# Sheet1.net
KiCad netlist of a schematic drawn in Altium Designer
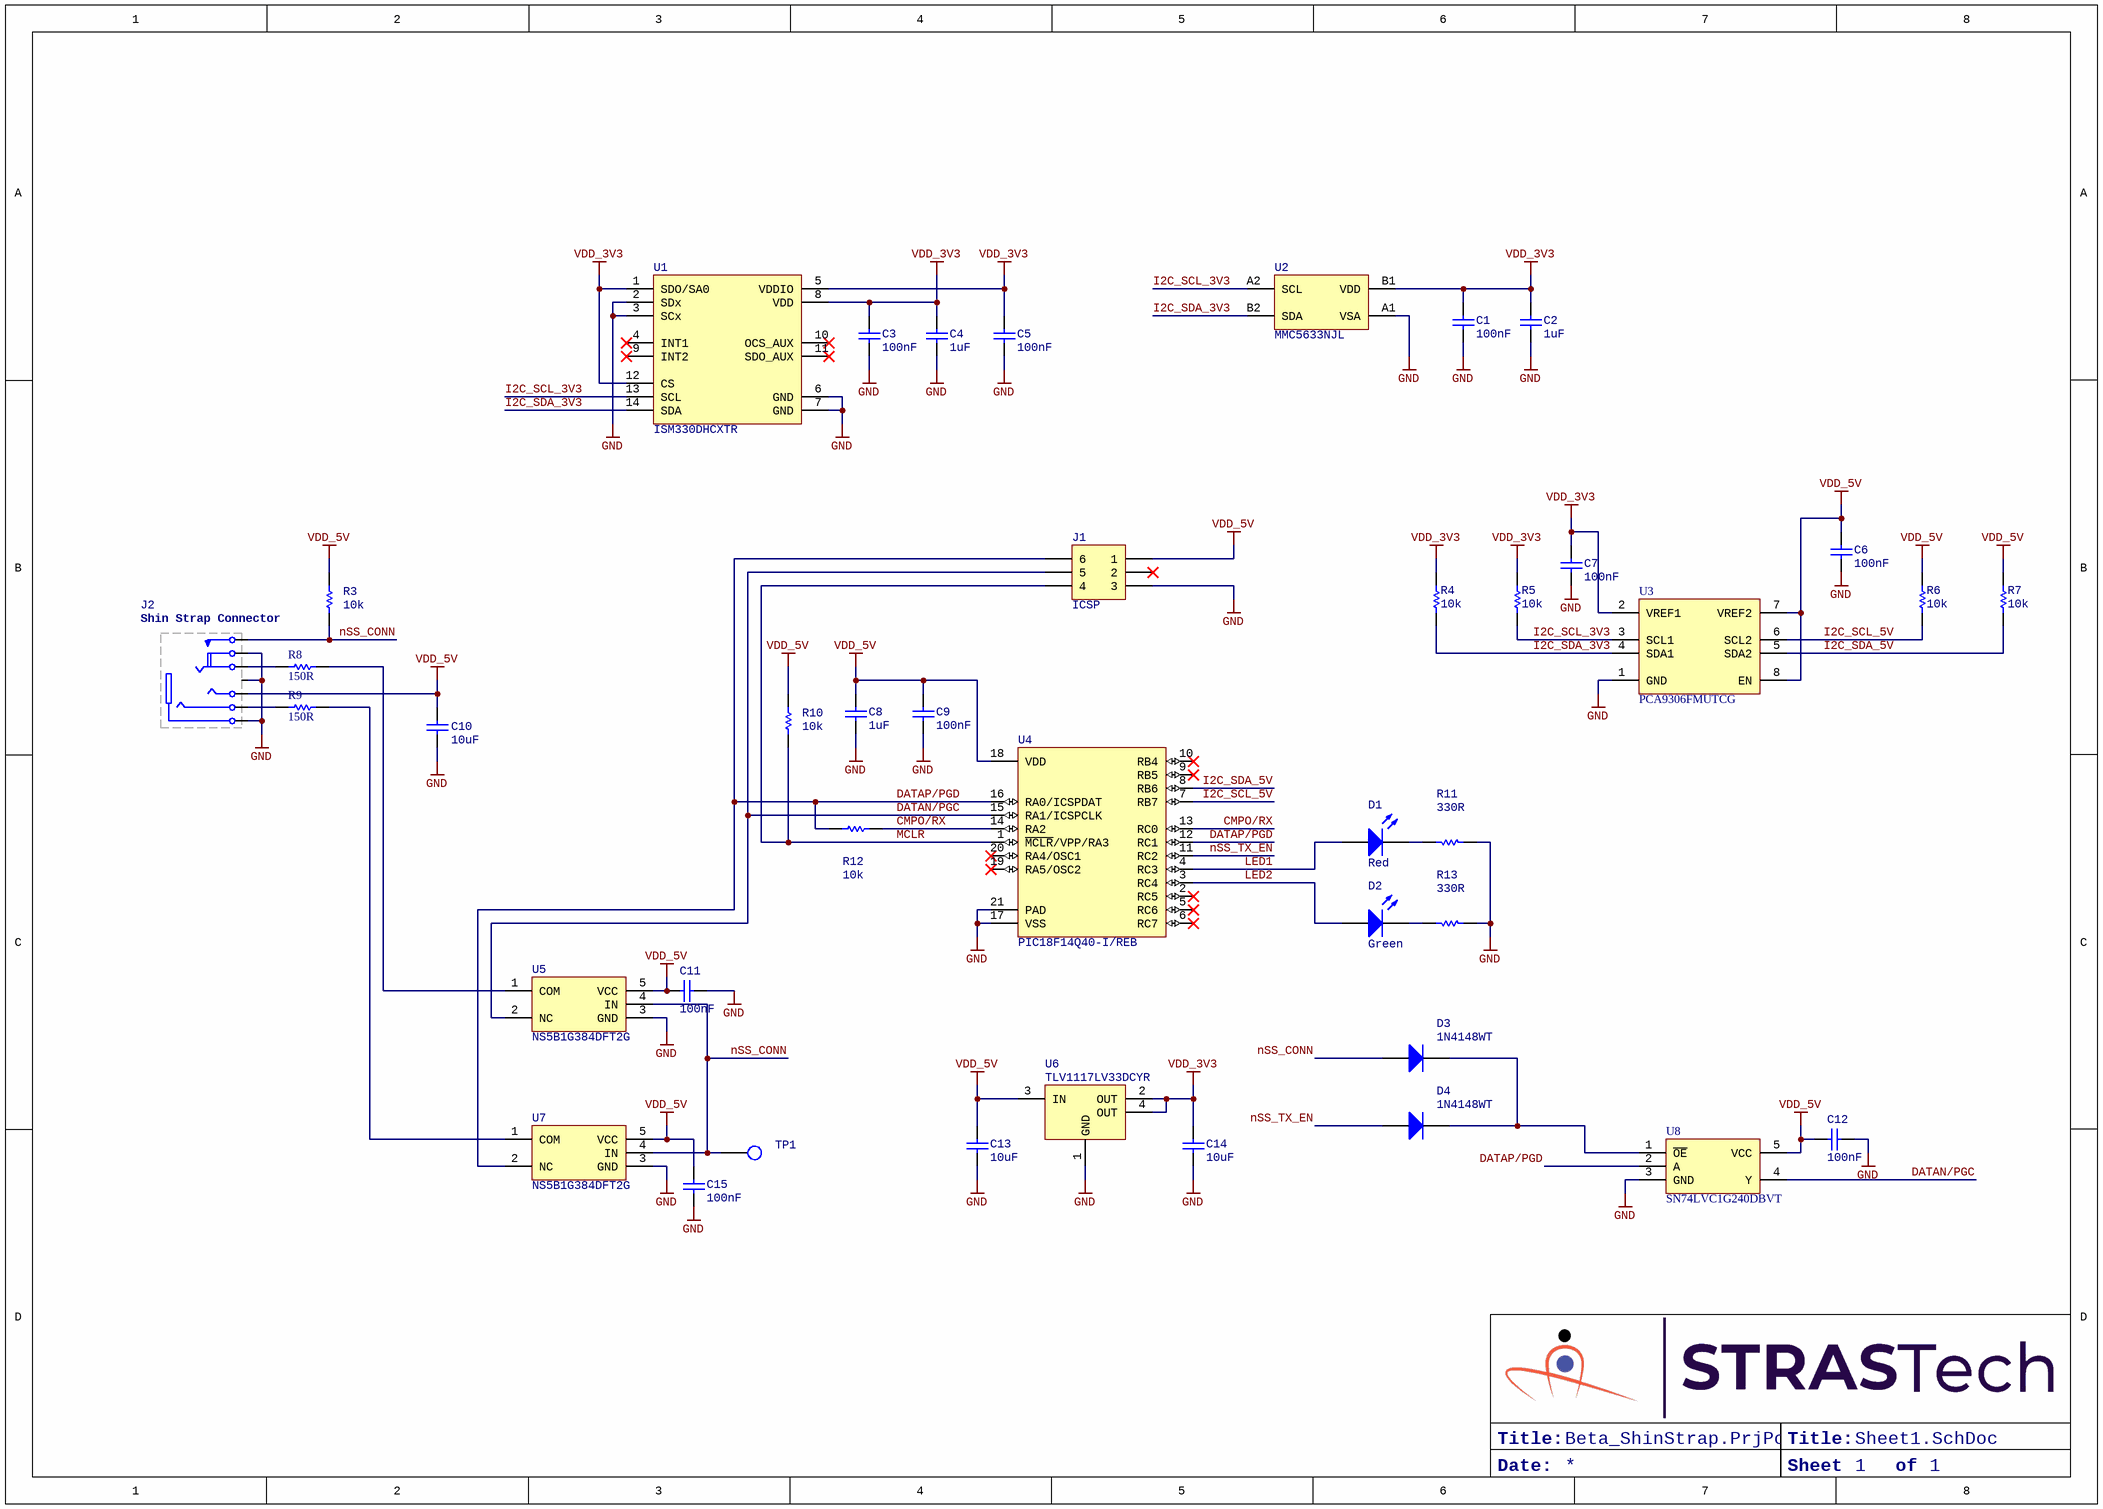
[diagram p0: Sheet1.SchDoc]

(export (version "E")
  (design (tool "Eeschema 10.0.6"))
  (components
    (comp (ref "C1")
      (value "100nF")
      (footprint "Cap,SMD,0402")
      (description "0.1µF ±10% 25V Ceramic Capacitor X7R 0402 (1005 Metric)")
      (fields
        (field (name "VENDOR PART NUMBER") "490-14603-1-ND")
        (field (name "MANUFACTURER") "Murata Electronics")
        (field (name "CREATEDBY") "Judd Foster")
      )
      (libsource (lib "symbols") (part "CAP,Cer,100nF,25VDC,X7R,0402"))
    )
    (comp (ref "C2")
      (value "1uF")
      (footprint "Cap,SMD,0402")
      (description "1 µF ±10% 35V Ceramic Capacitor X5R 0402 (1005 Metric)")
      (fields
        (field (name "VENDOR PART NUMBER") "445-9073-1-ND")
        (field (name "MANUFACTURER") "TDK Corporation")
        (field (name "CREATEDBY") "Judd Foster")
      )
      (libsource (lib "symbols") (part "CAP,Cer,1uF,35VDC,X5R,0402"))
    )
    (comp (ref "C3")
      (value "100nF")
      (footprint "Cap,SMD,0402")
      (description "0.1µF ±10% 25V Ceramic Capacitor X7R 0402 (1005 Metric)")
      (fields
        (field (name "VENDOR PART NUMBER") "490-14603-1-ND")
        (field (name "MANUFACTURER") "Murata Electronics")
        (field (name "CREATEDBY") "Judd Foster")
      )
      (libsource (lib "symbols") (part "CAP,Cer,100nF,25VDC,X7R,0402"))
    )
    (comp (ref "C4")
      (value "1uF")
      (footprint "Cap,SMD,0402")
      (description "1 µF ±10% 35V Ceramic Capacitor X5R 0402 (1005 Metric)")
      (fields
        (field (name "VENDOR PART NUMBER") "445-9073-1-ND")
        (field (name "MANUFACTURER") "TDK Corporation")
        (field (name "CREATEDBY") "Judd Foster")
      )
      (libsource (lib "symbols") (part "CAP,Cer,1uF,35VDC,X5R,0402"))
    )
    (comp (ref "C5")
      (value "100nF")
      (footprint "Cap,SMD,0402")
      (description "0.1µF ±10% 25V Ceramic Capacitor X7R 0402 (1005 Metric)")
      (fields
        (field (name "VENDOR PART NUMBER") "490-14603-1-ND")
        (field (name "MANUFACTURER") "Murata Electronics")
        (field (name "CREATEDBY") "Judd Foster")
      )
      (libsource (lib "symbols") (part "CAP,Cer,100nF,25VDC,X7R,0402"))
    )
    (comp (ref "C6")
      (value "100nF")
      (footprint "Cap,SMD,0402")
      (description "0.1µF ±10% 25V Ceramic Capacitor X7R 0402 (1005 Metric)")
      (fields
        (field (name "VENDOR PART NUMBER") "490-14603-1-ND")
        (field (name "MANUFACTURER") "Murata Electronics")
        (field (name "CREATEDBY") "Judd Foster")
      )
      (libsource (lib "symbols") (part "CAP,Cer,100nF,25VDC,X7R,0402"))
    )
    (comp (ref "C7")
      (value "100nF")
      (footprint "Cap,SMD,0402")
      (description "0.1µF ±10% 25V Ceramic Capacitor X7R 0402 (1005 Metric)")
      (fields
        (field (name "VENDOR PART NUMBER") "490-14603-1-ND")
        (field (name "MANUFACTURER") "Murata Electronics")
        (field (name "CREATEDBY") "Judd Foster")
      )
      (libsource (lib "symbols") (part "CAP,Cer,100nF,25VDC,X7R,0402"))
    )
    (comp (ref "C8")
      (value "1uF")
      (footprint "Cap,SMD,0402")
      (description "1 µF ±10% 35V Ceramic Capacitor X5R 0402 (1005 Metric)")
      (fields
        (field (name "VENDOR PART NUMBER") "445-9073-1-ND")
        (field (name "MANUFACTURER") "TDK Corporation")
        (field (name "CREATEDBY") "Judd Foster")
      )
      (libsource (lib "symbols") (part "CAP,Cer,1uF,35VDC,X5R,0402"))
    )
    (comp (ref "C9")
      (value "100nF")
      (footprint "Cap,SMD,0402")
      (description "0.1µF ±10% 25V Ceramic Capacitor X7R 0402 (1005 Metric)")
      (fields
        (field (name "VENDOR PART NUMBER") "490-14603-1-ND")
        (field (name "MANUFACTURER") "Murata Electronics")
        (field (name "CREATEDBY") "Judd Foster")
      )
      (libsource (lib "symbols") (part "CAP,Cer,100nF,25VDC,X7R,0402"))
    )
    (comp (ref "C10")
      (value "10uF")
      (footprint "Cap,SMD,0402")
      (description "10 µF ±20% 10V Ceramic Capacitor X5R 0402 (1005 Metric)")
      (fields
        (field (name "VENDOR PART NUMBER") "1276-1450-1-ND")
        (field (name "MANUFACTURER") "Samsung Electro-Mechanics")
        (field (name "CREATEDBY") "Judd Foster")
      )
      (libsource (lib "symbols") (part "CAP,Cer,10uF,10VDC,X5R,0402"))
    )
    (comp (ref "C11")
      (value "100nF")
      (footprint "Cap,SMD,0402")
      (description "0.1µF ±10% 25V Ceramic Capacitor X7R 0402 (1005 Metric)")
      (fields
        (field (name "VENDOR PART NUMBER") "490-14603-1-ND")
        (field (name "MANUFACTURER") "Murata Electronics")
        (field (name "CREATEDBY") "Judd Foster")
      )
      (libsource (lib "symbols") (part "CAP,Cer,100nF,25VDC,X7R,0402"))
    )
    (comp (ref "C12")
      (value "100nF")
      (footprint "Cap,SMD,0402")
      (description "0.1µF ±10% 25V Ceramic Capacitor X7R 0402 (1005 Metric)")
      (fields
        (field (name "VENDOR PART NUMBER") "490-14603-1-ND")
        (field (name "MANUFACTURER") "Murata Electronics")
        (field (name "CREATEDBY") "Judd Foster")
      )
      (libsource (lib "symbols") (part "CAP,Cer,100nF,25VDC,X7R,0402"))
    )
    (comp (ref "C13")
      (value "10uF")
      (footprint "Cap,SMD,0402")
      (description "10 µF ±20% 10V Ceramic Capacitor X5R 0402 (1005 Metric)")
      (fields
        (field (name "VENDOR PART NUMBER") "1276-1450-1-ND")
        (field (name "MANUFACTURER") "Samsung Electro-Mechanics")
        (field (name "CREATEDBY") "Judd Foster")
      )
      (libsource (lib "symbols") (part "CAP,Cer,10uF,10VDC,X5R,0402"))
    )
    (comp (ref "C14")
      (value "10uF")
      (footprint "Cap,SMD,0402")
      (description "10 µF ±20% 10V Ceramic Capacitor X5R 0402 (1005 Metric)")
      (fields
        (field (name "VENDOR PART NUMBER") "1276-1450-1-ND")
        (field (name "MANUFACTURER") "Samsung Electro-Mechanics")
        (field (name "CREATEDBY") "Judd Foster")
      )
      (libsource (lib "symbols") (part "CAP,Cer,10uF,10VDC,X5R,0402"))
    )
    (comp (ref "C15")
      (value "100nF")
      (footprint "Cap,SMD,0402")
      (description "0.1µF ±10% 25V Ceramic Capacitor X7R 0402 (1005 Metric)")
      (fields
        (field (name "VENDOR PART NUMBER") "490-14603-1-ND")
        (field (name "MANUFACTURER") "Murata Electronics")
        (field (name "CREATEDBY") "Judd Foster")
      )
      (libsource (lib "symbols") (part "CAP,Cer,100nF,25VDC,X7R,0402"))
    )
    (comp (ref "D1")
      (value "Red")
      (footprint "LED,0603")
      (description "Red 633nm LED Indication - Discrete 2V 0603 (1608 Metric)")
      (fields
        (field (name "MANUFACTURER") "Lite-On Inc.")
        (field (name "MANUFACTURER PART NUMBER") "LS Q976-NR-1")
        (field (name "CREATEDBY") "Judd Foster")
      )
      (libsource (lib "symbols") (part "LED,Red,SMD,0603"))
    )
    (comp (ref "D2")
      (value "Green")
      (footprint "LED,0603")
      (description "Green 530nm LED Indication - Discrete 3V 0603 (1608 Metric)")
      (fields
        (field (name "MANUFACTURER") "Stanley Electric Co")
        (field (name "MANUFACTURER PART NUMBER") "THG1111C-0005-TR")
        (field (name "CREATEDBY") "Judd Foster")
      )
      (libsource (lib "symbols") (part "LED,Green,SMD,0603"))
    )
    (comp (ref "D3")
      (value "1N4148WT")
      (footprint "SOD523")
      (description "Diode Standard 75 V 200mA Surface Mount SOD-523F")
      (fields
        (field (name "MANUFACTURER") "ON Semiconductor")
        (field (name "VENDOR PART NUMBER") "1N4148WTCT-ND")
        (field (name "CREATEDBY") "Judd Foster")
      )
      (libsource (lib "symbols") (part "DIODE,Gen,75V,200mA,SOD523F"))
    )
    (comp (ref "D4")
      (value "1N4148WT")
      (footprint "SOD523")
      (description "Diode Standard 75 V 200mA Surface Mount SOD-523F")
      (fields
        (field (name "MANUFACTURER") "ON Semiconductor")
        (field (name "VENDOR PART NUMBER") "1N4148WTCT-ND")
        (field (name "CREATEDBY") "Judd Foster")
      )
      (libsource (lib "symbols") (part "DIODE,Gen,75V,200mA,SOD523F"))
    )
    (comp (ref "J1")
      (value "Term,Header,3x2 Pin,1.27mm,SMD")
      (footprint "TERM,HEADER,3X2PIN,P1.27,SMD")
      (description "Connector Header Surface Mount 6 position 0.050\" (1.27mm)")
      (fields
        (field (name "VENDOR PART NUMBER") "609-3693-1-ND")
        (field (name "MANUFACTURER") "Amphenol ICC (FCI)")
        (field (name "CREATEDBY") "Judd Foster")
      )
      (libsource (lib "symbols") (part "Term,Header,3x2 Pin,1.27mm,SMD"))
    )
    (comp (ref "J2")
      (value "Conn,Jack,TRS,3.5mm,Thru,Shielded")
      (footprint "Conn,Jack,TRS,3.5mm,Thru,Shielded")
      (fields
        (field (name "MANUFACTURER") "CUI Devices")
        (field (name "MANUFACTURER PART NUMBER") "SJ-435107RS")
        (field (name "VENDOR PART NUMBER") "CP-435107RS-ND")
        (field (name "CREATEDBY") "Judd Foster")
      )
      (libsource (lib "symbols") (part "Conn,Jack,TRS,3.5mm,Thru,Shielded"))
    )
    (comp (ref "R3")
      (value "10k")
      (footprint "RES,0402")
      (description "10 kOhms ±5% 0.063W, 1/16W Chip Resistor 0402 (1005 Metric) Automotive AEC-Q200 Thick Film")
      (fields
        (field (name "VENDOR PART NUMBER") "RMCF0402JT10K0CT-ND")
        (field (name "MANUFACTURER") "Stackpole Electronics Inc")
        (field (name "CREATEDBY") "Judd Foster")
      )
      (libsource (lib "symbols") (part "RES,10k,5%,0.063W,0402"))
    )
    (comp (ref "R4")
      (value "10k")
      (footprint "RES,0402")
      (description "10 kOhms ±5% 0.063W, 1/16W Chip Resistor 0402 (1005 Metric) Automotive AEC-Q200 Thick Film")
      (fields
        (field (name "VENDOR PART NUMBER") "RMCF0402JT10K0CT-ND")
        (field (name "MANUFACTURER") "Stackpole Electronics Inc")
        (field (name "CREATEDBY") "Judd Foster")
      )
      (libsource (lib "symbols") (part "RES,10k,5%,0.063W,0402"))
    )
    (comp (ref "R5")
      (value "10k")
      (footprint "RES,0402")
      (description "10 kOhms ±5% 0.063W, 1/16W Chip Resistor 0402 (1005 Metric) Automotive AEC-Q200 Thick Film")
      (fields
        (field (name "VENDOR PART NUMBER") "RMCF0402JT10K0CT-ND")
        (field (name "MANUFACTURER") "Stackpole Electronics Inc")
        (field (name "CREATEDBY") "Judd Foster")
      )
      (libsource (lib "symbols") (part "RES,10k,5%,0.063W,0402"))
    )
    (comp (ref "R6")
      (value "10k")
      (footprint "RES,0402")
      (description "10 kOhms ±5% 0.063W, 1/16W Chip Resistor 0402 (1005 Metric) Automotive AEC-Q200 Thick Film")
      (fields
        (field (name "VENDOR PART NUMBER") "RMCF0402JT10K0CT-ND")
        (field (name "MANUFACTURER") "Stackpole Electronics Inc")
        (field (name "CREATEDBY") "Judd Foster")
      )
      (libsource (lib "symbols") (part "RES,10k,5%,0.063W,0402"))
    )
    (comp (ref "R7")
      (value "10k")
      (footprint "RES,0402")
      (description "10 kOhms ±5% 0.063W, 1/16W Chip Resistor 0402 (1005 Metric) Automotive AEC-Q200 Thick Film")
      (fields
        (field (name "VENDOR PART NUMBER") "RMCF0402JT10K0CT-ND")
        (field (name "MANUFACTURER") "Stackpole Electronics Inc")
        (field (name "CREATEDBY") "Judd Foster")
      )
      (libsource (lib "symbols") (part "RES,10k,5%,0.063W,0402"))
    )
    (comp (ref "R8")
      (value "150R")
      (footprint "RES,0402")
      (fields
        (field (name "MANUFACTURER") "TE Connectivity Passive Product")
        (field (name "MANUFACTURER PART NUMBER") "CRGCQ0402F150R")
        (field (name "VENDOR PART NUMBER") "A129617CT-ND")
        (field (name "CREATEDBY") "Judd Foster")
      )
      (libsource (lib "symbols") (part "RES,150R,1%,0.1W,0402"))
    )
    (comp (ref "R9")
      (value "150R")
      (footprint "RES,0402")
      (fields
        (field (name "MANUFACTURER") "TE Connectivity Passive Product")
        (field (name "MANUFACTURER PART NUMBER") "CRGCQ0402F150R")
        (field (name "VENDOR PART NUMBER") "A129617CT-ND")
        (field (name "CREATEDBY") "Judd Foster")
      )
      (libsource (lib "symbols") (part "RES,150R,1%,0.1W,0402"))
    )
    (comp (ref "R10")
      (value "10k")
      (footprint "RES,0402")
      (description "10 kOhms ±5% 0.063W, 1/16W Chip Resistor 0402 (1005 Metric) Automotive AEC-Q200 Thick Film")
      (fields
        (field (name "VENDOR PART NUMBER") "RMCF0402JT10K0CT-ND")
        (field (name "MANUFACTURER") "Stackpole Electronics Inc")
        (field (name "CREATEDBY") "Judd Foster")
      )
      (libsource (lib "symbols") (part "RES,10k,5%,0.063W,0402"))
    )
    (comp (ref "R11")
      (value "330R")
      (footprint "RES,0402")
      (description "330 Ohms ±5% 0.063W, 1/16W Chip Resistor 0402 (1005 Metric) Automotive AEC-Q200 Thick Film")
      (fields
        (field (name "MANUFACTURER") "Stackpole Electronics Inc")
        (field (name "MANUFACTURER PART NUMBER") "RMCF0402JT330R")
        (field (name "CREATEDBY") "Judd Foster")
      )
      (libsource (lib "symbols") (part "RES,330R,5%,0.063W,0402"))
    )
    (comp (ref "R12")
      (value "10k")
      (footprint "RES,0402")
      (description "10 kOhms ±5% 0.063W, 1/16W Chip Resistor 0402 (1005 Metric) Automotive AEC-Q200 Thick Film")
      (fields
        (field (name "VENDOR PART NUMBER") "RMCF0402JT10K0CT-ND")
        (field (name "MANUFACTURER") "Stackpole Electronics Inc")
        (field (name "CREATEDBY") "Judd Foster")
      )
      (libsource (lib "symbols") (part "RES,10k,5%,0.063W,0402"))
    )
    (comp (ref "R13")
      (value "330R")
      (footprint "RES,0402")
      (description "330 Ohms ±5% 0.063W, 1/16W Chip Resistor 0402 (1005 Metric) Automotive AEC-Q200 Thick Film")
      (fields
        (field (name "MANUFACTURER") "Stackpole Electronics Inc")
        (field (name "MANUFACTURER PART NUMBER") "RMCF0402JT330R")
        (field (name "CREATEDBY") "Judd Foster")
      )
      (libsource (lib "symbols") (part "RES,330R,5%,0.063W,0402"))
    )
    (comp (ref "TP1")
      (value "TESTPOINT")
      (footprint "testpoint,smd,round,1mm")
      (description "PCB Testpoint")
      (fields (field (name "CREATEDBY") "Judd Foster"))
      (libsource (lib "symbols") (part "TESTPOINT"))
    )
    (comp (ref "U1")
      (value "ISM330DHCXTR")
      (footprint "IC,LGA-14L,2.5x3mm")
      (description "Accelerometer, Gyroscope, Temperature, 6 Axis Sensor I²C, SPI Output")
      (fields
        (field (name "MANUFACTURER") "STMicroelectronics")
        (field (name "VENDOR PART NUMBER") "497-19784-1-ND")
        (field (name "CREATEDBY") "Judd Foster")
      )
      (libsource (lib "symbols") (part "ISM330DHCXTR"))
    )
    (comp (ref "U2")
      (value "MMC5633NJL")
      (footprint "IC,WLP,2x2,P0.4mm")
      (description "Magnetoresistive Sensor X, Y, Z Axis 4-WLP (0.85x0.85)")
      (fields
        (field (name "MANUFACTURER") "Memsic Inc.")
        (field (name "VENDOR PART NUMBER") "1267-MMC5633NJLCT-ND")
        (field (name "CREATEDBY") "Judd Foster")
      )
      (libsource (lib "symbols") (part "MMC5633NJL"))
    )
    (comp (ref "U3")
      (value "PCA9306FMUTCG")
      (footprint "IC,UDFN-8,P0.35")
      (description "Voltage Level Translator Bidirectional 1 Circuit 2 Channel 8-UDFN (1.45x1)")
      (fields
        (field (name "MANUFACTURER") "onsemi")
        (field (name "VENDOR PART NUMBER") "PCA9306FMUTCGOSCT-ND")
        (field (name "CREATEDBY") "Judd Foster")
      )
      (libsource (lib "symbols") (part "PCA9306FMUTCG"))
    )
    (comp (ref "U4")
      (value "PIC18F14Q40-I/REB")
      (footprint "IC,QFN-20,3x3,PAD,P0.4")
      (description "PIC series Microcontroller IC 8-Bit 64MHz 16KB (16K x 8) FLASH 20-VQFN (3x3)")
      (fields
        (field (name "MANUFACTURER") "Microchip Technology")
        (field (name "VENDOR PART NUMBER") "150-PIC18F14Q40-I/REB-ND")
        (field (name "CREATEDBY") "Judd Foster")
      )
      (libsource (lib "symbols") (part "PIC18F14Q40-I/REB"))
    )
    (comp (ref "U5")
      (value "NS5B1G384DFT2G")
      (footprint "SC70-5")
      (description "1 Circuit IC Switch 1:1 15Ohm SC-88A (SC-70-5/SOT-353)")
      (fields
        (field (name "MANUFACTURER") "onsemi")
        (field (name "VENDOR PART NUMBER") "NS5B1G384DFT2GOSCT-ND")
        (field (name "CREATEDBY") "Judd Foster")
      )
      (libsource (lib "symbols") (part "NS5B1G384DFT2G"))
    )
    (comp (ref "U6")
      (value "TLV1117LV33DCYR")
      (footprint "SOT223")
      (description "Linear Voltage Regulator IC  1 Output  1A SOT-223-4")
      (fields
        (field (name "MANUFACTURER") "Texas Instruments")
        (field (name "VENDOR PART NUMBER") "296-28778-1-ND")
        (field (name "CREATEDBY") "Judd Foster")
      )
      (libsource (lib "symbols") (part "TLV1117LV33DCYR"))
    )
    (comp (ref "U7")
      (value "NS5B1G384DFT2G")
      (footprint "SC70-5")
      (description "1 Circuit IC Switch 1:1 15Ohm SC-88A (SC-70-5/SOT-353)")
      (fields
        (field (name "MANUFACTURER") "onsemi")
        (field (name "VENDOR PART NUMBER") "NS5B1G384DFT2GOSCT-ND")
        (field (name "CREATEDBY") "Judd Foster")
      )
      (libsource (lib "symbols") (part "NS5B1G384DFT2G"))
    )
    (comp (ref "U8")
      (value "SN74LVC1G240DBVT")
      (footprint "sot23-5")
      (description "Buffer, Inverting 1 Element 1 Bit per Element 3-State Output SOT-23-5")
      (fields
        (field (name "VENDOR PART NUMBER") "296-32301-1-ND")
        (field (name "MANUFACTURER") "Texas Instruments")
        (field (name "CREATEDBY") "Judd Foster")
      )
      (libsource (lib "symbols") (part "SN74LVC1G240DBVT"))
    )
  )
  (nets
    (net (code "1") (name "/CMPO{slash}RX") (class "Default")
      (node (ref "R12") (pin "1") (pinfunction "1_1") (pintype "passive"))
      (node (ref "U4") (pin "13") (pinfunction "RC0_13") (pintype "bidirectional"))
      (node (ref "U4") (pin "14") (pinfunction "RA2_14") (pintype "bidirectional"))
    )
    (net (code "2") (name "/DATAN{slash}PGC") (class "Default")
      (node (ref "J1") (pin "5") (pinfunction "5_5") (pintype "passive"))
      (node (ref "U4") (pin "15") (pinfunction "RA1/ICSPCLK_15") (pintype "bidirectional"))
      (node (ref "U5") (pin "2") (pinfunction "NC_2") (pintype "passive"))
      (node (ref "U8") (pin "4") (pinfunction "Y_4") (pintype "passive"))
    )
    (net (code "3") (name "/DATAP{slash}PGD") (class "Default")
      (node (ref "J1") (pin "6") (pinfunction "6_6") (pintype "passive"))
      (node (ref "R12") (pin "2") (pinfunction "2_2") (pintype "passive"))
      (node (ref "U4") (pin "12") (pinfunction "RC1_12") (pintype "bidirectional"))
      (node (ref "U4") (pin "16") (pinfunction "RA0/ICSPDAT_16") (pintype "bidirectional"))
      (node (ref "U7") (pin "2") (pinfunction "NC_2") (pintype "passive"))
      (node (ref "U8") (pin "2") (pinfunction "A_2") (pintype "passive"))
    )
    (net (code "4") (name "/I2C_SCL_3V3") (class "Default")
      (node (ref "R5") (pin "1") (pinfunction "1_1") (pintype "passive"))
      (node (ref "U1") (pin "13") (pinfunction "SCL_13") (pintype "passive"))
      (node (ref "U2") (pin "A2") (pinfunction "SCL_A2") (pintype "passive"))
      (node (ref "U3") (pin "3") (pinfunction "SCL1_3") (pintype "passive"))
    )
    (net (code "5") (name "/I2C_SCL_5V") (class "Default")
      (node (ref "R6") (pin "1") (pinfunction "1_1") (pintype "passive"))
      (node (ref "U3") (pin "6") (pinfunction "SCL2_6") (pintype "passive"))
      (node (ref "U4") (pin "7") (pinfunction "RB7_7") (pintype "bidirectional"))
    )
    (net (code "6") (name "/I2C_SDA_3V3") (class "Default")
      (node (ref "R4") (pin "1") (pinfunction "1_1") (pintype "passive"))
      (node (ref "U1") (pin "14") (pinfunction "SDA_14") (pintype "passive"))
      (node (ref "U2") (pin "B2") (pinfunction "SDA_B2") (pintype "passive"))
      (node (ref "U3") (pin "4") (pinfunction "SDA1_4") (pintype "passive"))
    )
    (net (code "7") (name "/I2C_SDA_5V") (class "Default")
      (node (ref "R7") (pin "1") (pinfunction "1_1") (pintype "passive"))
      (node (ref "U3") (pin "5") (pinfunction "SDA2_5") (pintype "passive"))
      (node (ref "U4") (pin "8") (pinfunction "RB6_8") (pintype "bidirectional"))
    )
    (net (code "8") (name "/LED1") (class "Default")
      (node (ref "D1") (pin "1") (pinfunction "A_1") (pintype "passive"))
      (node (ref "U4") (pin "4") (pinfunction "RC3_4") (pintype "bidirectional"))
    )
    (net (code "9") (name "/LED2") (class "Default")
      (node (ref "D2") (pin "1") (pinfunction "A_1") (pintype "passive"))
      (node (ref "U4") (pin "3") (pinfunction "RC4_3") (pintype "bidirectional"))
    )
    (net (code "10") (name "/nSS_CONN") (class "Default")
      (node (ref "D3") (pin "2") (pinfunction "A_2") (pintype "passive"))
      (node (ref "J2") (pin "6") (pinfunction "R1S_6") (pintype "passive"))
      (node (ref "R3") (pin "1") (pinfunction "1_1") (pintype "passive"))
      (node (ref "TP1") (pin "1") (pinfunction "TP_1") (pintype "passive"))
      (node (ref "U5") (pin "4") (pinfunction "IN_4") (pintype "passive"))
      (node (ref "U7") (pin "4") (pinfunction "IN_4") (pintype "passive"))
    )
    (net (code "11") (name "/nSS_TX_EN") (class "Default")
      (node (ref "D4") (pin "2") (pinfunction "A_2") (pintype "passive"))
      (node (ref "U4") (pin "11") (pinfunction "RC2_11") (pintype "bidirectional"))
    )
    (net (code "12") (name "/~{MCLR}") (class "Default")
      (node (ref "J1") (pin "4") (pinfunction "4_4") (pintype "passive"))
      (node (ref "R10") (pin "1") (pinfunction "1_1") (pintype "passive"))
      (node (ref "U4") (pin "1") (pinfunction "~{MCLR}/VPP/RA3_1") (pintype "bidirectional"))
    )
    (net (code "13") (name "GND") (class "Default")
      (node (ref "C1") (pin "2") (pinfunction "2_2") (pintype "passive"))
      (node (ref "C10") (pin "1") (pinfunction "1_1") (pintype "passive"))
      (node (ref "C11") (pin "2") (pinfunction "2_2") (pintype "passive"))
      (node (ref "C12") (pin "1") (pinfunction "1_1") (pintype "passive"))
      (node (ref "C13") (pin "1") (pinfunction "1_1") (pintype "passive"))
      (node (ref "C14") (pin "1") (pinfunction "1_1") (pintype "passive"))
      (node (ref "C15") (pin "1") (pinfunction "1_1") (pintype "passive"))
      (node (ref "C2") (pin "1") (pinfunction "1_1") (pintype "passive"))
      (node (ref "C3") (pin "1") (pinfunction "1_1") (pintype "passive"))
      (node (ref "C4") (pin "1") (pinfunction "1_1") (pintype "passive"))
      (node (ref "C5") (pin "1") (pinfunction "1_1") (pintype "passive"))
      (node (ref "C6") (pin "2") (pinfunction "2_2") (pintype "passive"))
      (node (ref "C7") (pin "2") (pinfunction "2_2") (pintype "passive"))
      (node (ref "C8") (pin "1") (pinfunction "1_1") (pintype "passive"))
      (node (ref "C9") (pin "1") (pinfunction "1_1") (pintype "passive"))
      (node (ref "J1") (pin "3") (pinfunction "3_3") (pintype "passive"))
      (node (ref "J2") (pin "0") (pinfunction "SH_0") (pintype "power_in"))
      (node (ref "J2") (pin "1") (pinfunction "S_1") (pintype "power_in"))
      (node (ref "J2") (pin "5") (pinfunction "IR1_5") (pintype "passive"))
      (node (ref "R11") (pin "1") (pinfunction "1_1") (pintype "passive"))
      (node (ref "R13") (pin "1") (pinfunction "1_1") (pintype "passive"))
      (node (ref "U1") (pin "2") (pinfunction "SDx_2") (pintype "passive"))
      (node (ref "U1") (pin "3") (pinfunction "SCx_3") (pintype "passive"))
      (node (ref "U1") (pin "6") (pinfunction "GND_6") (pintype "passive"))
      (node (ref "U1") (pin "7") (pinfunction "GND_7") (pintype "passive"))
      (node (ref "U2") (pin "A1") (pinfunction "VSA_A1") (pintype "passive"))
      (node (ref "U3") (pin "1") (pinfunction "GND_1") (pintype "passive"))
      (node (ref "U4") (pin "17") (pinfunction "VSS_17") (pintype "power_in"))
      (node (ref "U4") (pin "21") (pinfunction "PAD_21") (pintype "passive"))
      (node (ref "U5") (pin "3") (pinfunction "GND_3") (pintype "passive"))
      (node (ref "U6") (pin "1") (pinfunction "GND_1") (pintype "passive"))
      (node (ref "U7") (pin "3") (pinfunction "GND_3") (pintype "passive"))
      (node (ref "U8") (pin "3") (pinfunction "GND_3") (pintype "passive"))
    )
    (net (code "14") (name "Net-(D1-K)") (class "Default")
      (node (ref "D1") (pin "2") (pinfunction "K_2") (pintype "passive"))
      (node (ref "R11") (pin "2") (pinfunction "2_2") (pintype "passive"))
    )
    (net (code "15") (name "Net-(D2-K)") (class "Default")
      (node (ref "D2") (pin "2") (pinfunction "K_2") (pintype "passive"))
      (node (ref "R13") (pin "2") (pinfunction "2_2") (pintype "passive"))
    )
    (net (code "16") (name "Net-(D3-K)") (class "Default")
      (node (ref "D3") (pin "1") (pinfunction "K_1") (pintype "passive"))
      (node (ref "D4") (pin "1") (pinfunction "K_1") (pintype "passive"))
      (node (ref "U8") (pin "1") (pinfunction "~{OE}_1") (pintype "passive"))
    )
    (net (code "17") (name "Net-(J2-R1)") (class "Default")
      (node (ref "J2") (pin "3") (pinfunction "R1_3") (pintype "passive"))
      (node (ref "R8") (pin "1") (pinfunction "1_1") (pintype "passive"))
    )
    (net (code "18") (name "Net-(J2-R2)") (class "Default")
      (node (ref "J2") (pin "4") (pinfunction "R2_4") (pintype "passive"))
      (node (ref "R9") (pin "1") (pinfunction "1_1") (pintype "passive"))
    )
    (net (code "19") (name "Net-(U5-COM)") (class "Default")
      (node (ref "R8") (pin "2") (pinfunction "2_2") (pintype "passive"))
      (node (ref "U5") (pin "1") (pinfunction "COM_1") (pintype "passive"))
    )
    (net (code "20") (name "Net-(U7-COM)") (class "Default")
      (node (ref "R9") (pin "2") (pinfunction "2_2") (pintype "passive"))
      (node (ref "U7") (pin "1") (pinfunction "COM_1") (pintype "passive"))
    )
    (net (code "21") (name "VDD_3V3") (class "Default")
      (node (ref "C1") (pin "1") (pinfunction "1_1") (pintype "passive"))
      (node (ref "C14") (pin "2") (pinfunction "2_2") (pintype "passive"))
      (node (ref "C2") (pin "2") (pinfunction "2_2") (pintype "passive"))
      (node (ref "C3") (pin "2") (pinfunction "2_2") (pintype "passive"))
      (node (ref "C4") (pin "2") (pinfunction "2_2") (pintype "passive"))
      (node (ref "C5") (pin "2") (pinfunction "2_2") (pintype "passive"))
      (node (ref "C7") (pin "1") (pinfunction "1_1") (pintype "passive"))
      (node (ref "R4") (pin "2") (pinfunction "2_2") (pintype "passive"))
      (node (ref "R5") (pin "2") (pinfunction "2_2") (pintype "passive"))
      (node (ref "U1") (pin "1") (pinfunction "SDO/SA0_1") (pintype "passive"))
      (node (ref "U1") (pin "12") (pinfunction "CS_12") (pintype "passive"))
      (node (ref "U1") (pin "5") (pinfunction "VDDIO_5") (pintype "passive"))
      (node (ref "U1") (pin "8") (pinfunction "VDD_8") (pintype "passive"))
      (node (ref "U2") (pin "B1") (pinfunction "VDD_B1") (pintype "passive"))
      (node (ref "U3") (pin "2") (pinfunction "VREF1_2") (pintype "passive"))
      (node (ref "U6") (pin "2") (pinfunction "OUT_2") (pintype "passive"))
      (node (ref "U6") (pin "4") (pinfunction "OUT_4") (pintype "passive"))
    )
    (net (code "22") (name "VDD_5V") (class "Default")
      (node (ref "C10") (pin "2") (pinfunction "2_2") (pintype "passive"))
      (node (ref "C11") (pin "1") (pinfunction "1_1") (pintype "passive"))
      (node (ref "C12") (pin "2") (pinfunction "2_2") (pintype "passive"))
      (node (ref "C13") (pin "2") (pinfunction "2_2") (pintype "passive"))
      (node (ref "C15") (pin "2") (pinfunction "2_2") (pintype "passive"))
      (node (ref "C6") (pin "1") (pinfunction "1_1") (pintype "passive"))
      (node (ref "C8") (pin "2") (pinfunction "2_2") (pintype "passive"))
      (node (ref "C9") (pin "2") (pinfunction "2_2") (pintype "passive"))
      (node (ref "J1") (pin "1") (pinfunction "1_1") (pintype "passive"))
      (node (ref "J2") (pin "2") (pinfunction "T_2") (pintype "passive"))
      (node (ref "R10") (pin "2") (pinfunction "2_2") (pintype "passive"))
      (node (ref "R3") (pin "2") (pinfunction "2_2") (pintype "passive"))
      (node (ref "R6") (pin "2") (pinfunction "2_2") (pintype "passive"))
      (node (ref "R7") (pin "2") (pinfunction "2_2") (pintype "passive"))
      (node (ref "U3") (pin "7") (pinfunction "VREF2_7") (pintype "passive"))
      (node (ref "U3") (pin "8") (pinfunction "EN_8") (pintype "passive"))
      (node (ref "U4") (pin "18") (pinfunction "VDD_18") (pintype "power_in"))
      (node (ref "U5") (pin "5") (pinfunction "VCC_5") (pintype "passive"))
      (node (ref "U6") (pin "3") (pinfunction "IN_3") (pintype "passive"))
      (node (ref "U7") (pin "5") (pinfunction "VCC_5") (pintype "passive"))
      (node (ref "U8") (pin "5") (pinfunction "VCC_5") (pintype "passive"))
    )
    (net (code "23") (name "unconnected-(J1-Pad2)") (class "Default")
      (node (ref "J1") (pin "2") (pinfunction "2_2") (pintype "passive+no_connect"))
    )
    (net (code "24") (name "unconnected-(U1-INT1-Pad4)") (class "Default")
      (node (ref "U1") (pin "4") (pinfunction "INT1_4") (pintype "passive+no_connect"))
    )
    (net (code "25") (name "unconnected-(U1-INT2-Pad9)") (class "Default")
      (node (ref "U1") (pin "9") (pinfunction "INT2_9") (pintype "passive+no_connect"))
    )
    (net (code "26") (name "unconnected-(U1-OCS_AUX-Pad10)") (class "Default")
      (node (ref "U1") (pin "10") (pinfunction "OCS_AUX_10") (pintype "passive+no_connect"))
    )
    (net (code "27") (name "unconnected-(U1-SDO_AUX-Pad11)") (class "Default")
      (node (ref "U1") (pin "11") (pinfunction "SDO_AUX_11") (pintype "passive+no_connect"))
    )
    (net (code "28") (name "unconnected-(U4-RA4{slash}OSC1-Pad20)") (class "Default")
      (node (ref "U4") (pin "20") (pinfunction "RA4/OSC1_20") (pintype "bidirectional+no_connect"))
    )
    (net (code "29") (name "unconnected-(U4-RA5{slash}OSC2-Pad19)") (class "Default")
      (node (ref "U4") (pin "19") (pinfunction "RA5/OSC2_19") (pintype "bidirectional+no_connect"))
    )
    (net (code "30") (name "unconnected-(U4-RB4-Pad10)") (class "Default")
      (node (ref "U4") (pin "10") (pinfunction "RB4_10") (pintype "bidirectional+no_connect"))
    )
    (net (code "31") (name "unconnected-(U4-RB5-Pad9)") (class "Default")
      (node (ref "U4") (pin "9") (pinfunction "RB5_9") (pintype "bidirectional+no_connect"))
    )
    (net (code "32") (name "unconnected-(U4-RC5-Pad2)") (class "Default")
      (node (ref "U4") (pin "2") (pinfunction "RC5_2") (pintype "bidirectional+no_connect"))
    )
    (net (code "33") (name "unconnected-(U4-RC6-Pad5)") (class "Default")
      (node (ref "U4") (pin "5") (pinfunction "RC6_5") (pintype "bidirectional+no_connect"))
    )
    (net (code "34") (name "unconnected-(U4-RC7-Pad6)") (class "Default")
      (node (ref "U4") (pin "6") (pinfunction "RC7_6") (pintype "bidirectional+no_connect"))
    )
  )
)
